# us_h.net
KiCad netlist of a schematic drawn in EAGLE
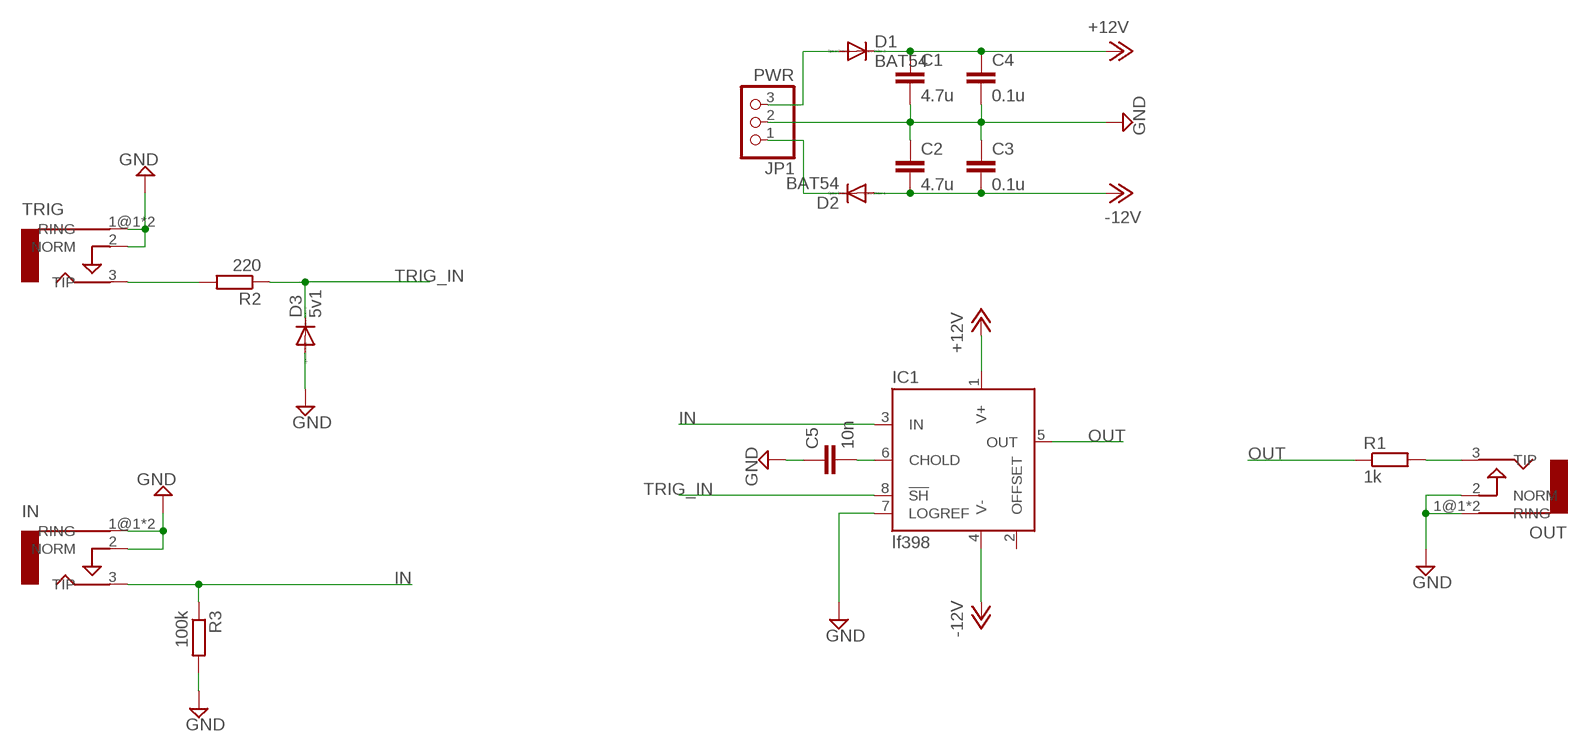
[diagram p0: schematic, sheet 1]

(export (version "E")
  (design (tool "Eeschema 10.0.6"))
  (components
    (comp (ref "C1")
      (value "4.7u")
      (footprint "eagle-import:C0805")
      (libsource (lib "eagle-import") (part "C-EUC0805"))
    )
    (comp (ref "C2")
      (value "4.7u")
      (footprint "eagle-import:C0805")
      (libsource (lib "eagle-import") (part "C-EUC0805"))
    )
    (comp (ref "C3")
      (value "0.1u")
      (footprint "eagle-import:C0805")
      (libsource (lib "eagle-import") (part "C-EUC0805"))
    )
    (comp (ref "C4")
      (value "0.1u")
      (footprint "eagle-import:C0805")
      (libsource (lib "eagle-import") (part "C-EUC0805"))
    )
    (comp (ref "C5")
      (value "10n")
      (footprint "eagle-import:C050-025X075")
      (libsource (lib "eagle-import") (part "C-EU050-025X075"))
    )
    (comp (ref "D1")
      (value "BAT54")
      (footprint "eagle-import:SOD323-W")
      (libsource (lib "eagle-import") (part "DIODE-SOD323-W"))
    )
    (comp (ref "D2")
      (value "BAT54")
      (footprint "eagle-import:SOD323-W")
      (libsource (lib "eagle-import") (part "DIODE-SOD323-W"))
    )
    (comp (ref "D3")
      (value "5v1")
      (footprint "eagle-import:SOD323-W")
      (libsource (lib "eagle-import") (part "DIODE-SOD323-W"))
    )
    (comp (ref "IC1")
      (value "lf398")
      (footprint "eagle-import:SO08")
      (libsource (lib "eagle-import") (part "LF398AD"))
    )
    (comp (ref "IN")
      (value "in")
      (footprint "eagle-import:ERTHENVAR-JACK")
      (libsource (lib "eagle-import") (part "AUDIO-JACKERTHENVAR"))
    )
    (comp (ref "JP1")
      (value "PWR")
      (footprint "eagle-import:1X03")
      (libsource (lib "eagle-import") (part "PINHD-1X3"))
    )
    (comp (ref "OUT")
      (value "out")
      (footprint "eagle-import:ERTHENVAR-JACK")
      (libsource (lib "eagle-import") (part "AUDIO-JACKERTHENVAR"))
    )
    (comp (ref "R1")
      (value "1k")
      (footprint "eagle-import:R0805")
      (libsource (lib "eagle-import") (part "R-EU_R0805"))
    )
    (comp (ref "R2")
      (value "220")
      (footprint "eagle-import:R0805")
      (libsource (lib "eagle-import") (part "R-EU_R0805"))
    )
    (comp (ref "R3")
      (value "100k")
      (footprint "eagle-import:R0805")
      (libsource (lib "eagle-import") (part "R-EU_R0805"))
    )
    (comp (ref "TRIG")
      (value "trig")
      (footprint "eagle-import:ERTHENVAR-JACK")
      (libsource (lib "eagle-import") (part "AUDIO-JACKERTHENVAR"))
    )
  )
  (nets
    (net (code "1") (name "+12V") (class "Default")
      (node (ref "C1") (pin "1") (pinfunction "1_1") (pintype "passive"))
      (node (ref "C4") (pin "1") (pinfunction "1_1") (pintype "passive"))
      (node (ref "D1") (pin "C") (pinfunction "C_C") (pintype "passive"))
      (node (ref "IC1") (pin "1") (pinfunction "V+_1") (pintype "power_in"))
    )
    (net (code "2") (name "-12V") (class "Default")
      (node (ref "C2") (pin "2") (pinfunction "2_2") (pintype "passive"))
      (node (ref "C3") (pin "2") (pinfunction "2_2") (pintype "passive"))
      (node (ref "D2") (pin "A") (pinfunction "A_A") (pintype "passive"))
      (node (ref "IC1") (pin "4") (pinfunction "V-_4") (pintype "power_in"))
    )
    (net (code "3") (name "/IN") (class "Default")
      (node (ref "IC1") (pin "3") (pinfunction "IN_3") (pintype "input"))
      (node (ref "IN") (pin "3") (pinfunction "TIP_3") (pintype "bidirectional"))
      (node (ref "R3") (pin "1") (pinfunction "1_1") (pintype "passive"))
    )
    (net (code "4") (name "/OUT") (class "Default")
      (node (ref "IC1") (pin "5") (pinfunction "OUT_5") (pintype "output"))
      (node (ref "R1") (pin "1") (pinfunction "1_1") (pintype "passive"))
    )
    (net (code "5") (name "/TRIG_IN") (class "Default")
      (node (ref "D3") (pin "C") (pinfunction "C_C") (pintype "passive"))
      (node (ref "IC1") (pin "8") (pinfunction "~{SH}_8") (pintype "input"))
      (node (ref "R2") (pin "1") (pinfunction "1_1") (pintype "passive"))
    )
    (net (code "6") (name "GND") (class "Default")
      (node (ref "C1") (pin "2") (pinfunction "2_2") (pintype "passive"))
      (node (ref "C2") (pin "1") (pinfunction "1_1") (pintype "passive"))
      (node (ref "C3") (pin "1") (pinfunction "1_1") (pintype "passive"))
      (node (ref "C4") (pin "2") (pinfunction "2_2") (pintype "passive"))
      (node (ref "C5") (pin "1") (pinfunction "1_1") (pintype "passive"))
      (node (ref "D3") (pin "A") (pinfunction "A_A") (pintype "passive"))
      (node (ref "IC1") (pin "7") (pinfunction "LOGREF_7") (pintype "power_in"))
      (node (ref "IN") (pin "1@1") (pinfunction "RING_1@1") (pintype "bidirectional"))
      (node (ref "IN") (pin "1@2") (pinfunction "RING_1@2") (pintype "bidirectional"))
      (node (ref "IN") (pin "2") (pinfunction "NORM_2") (pintype "bidirectional"))
      (node (ref "JP1") (pin "2") (pinfunction "2_2") (pintype "passive"))
      (node (ref "OUT") (pin "1@1") (pinfunction "RING_1@1") (pintype "bidirectional"))
      (node (ref "OUT") (pin "1@2") (pinfunction "RING_1@2") (pintype "bidirectional"))
      (node (ref "OUT") (pin "2") (pinfunction "NORM_2") (pintype "bidirectional"))
      (node (ref "R3") (pin "2") (pinfunction "2_2") (pintype "passive"))
      (node (ref "TRIG") (pin "1@1") (pinfunction "RING_1@1") (pintype "bidirectional"))
      (node (ref "TRIG") (pin "1@2") (pinfunction "RING_1@2") (pintype "bidirectional"))
      (node (ref "TRIG") (pin "2") (pinfunction "NORM_2") (pintype "bidirectional"))
    )
    (net (code "7") (name "Net-(D1-PadA)") (class "Default")
      (node (ref "D1") (pin "A") (pinfunction "A_A") (pintype "passive"))
      (node (ref "JP1") (pin "3") (pinfunction "3_3") (pintype "passive"))
    )
    (net (code "8") (name "Net-(D2-PadC)") (class "Default")
      (node (ref "D2") (pin "C") (pinfunction "C_C") (pintype "passive"))
      (node (ref "JP1") (pin "1") (pinfunction "1_1") (pintype "passive"))
    )
    (net (code "9") (name "Net-(IC1-CHOLD)") (class "Default")
      (node (ref "C5") (pin "2") (pinfunction "2_2") (pintype "passive"))
      (node (ref "IC1") (pin "6") (pinfunction "CHOLD_6") (pintype "passive"))
    )
    (net (code "10") (name "Net-(OUT-TIP)") (class "Default")
      (node (ref "OUT") (pin "3") (pinfunction "TIP_3") (pintype "bidirectional"))
      (node (ref "R1") (pin "2") (pinfunction "2_2") (pintype "passive"))
    )
    (net (code "11") (name "Net-(TRIG-TIP)") (class "Default")
      (node (ref "R2") (pin "2") (pinfunction "2_2") (pintype "passive"))
      (node (ref "TRIG") (pin "3") (pinfunction "TIP_3") (pintype "bidirectional"))
    )
    (net (code "12") (name "unconnected-(IC1-OFFSET-Pad2)") (class "Default")
      (node (ref "IC1") (pin "2") (pinfunction "OFFSET_2") (pintype "input"))
    )
  )
)
